# LDAQ-MOD-DAC4.net
KiCad netlist of a schematic drawn in EAGLE
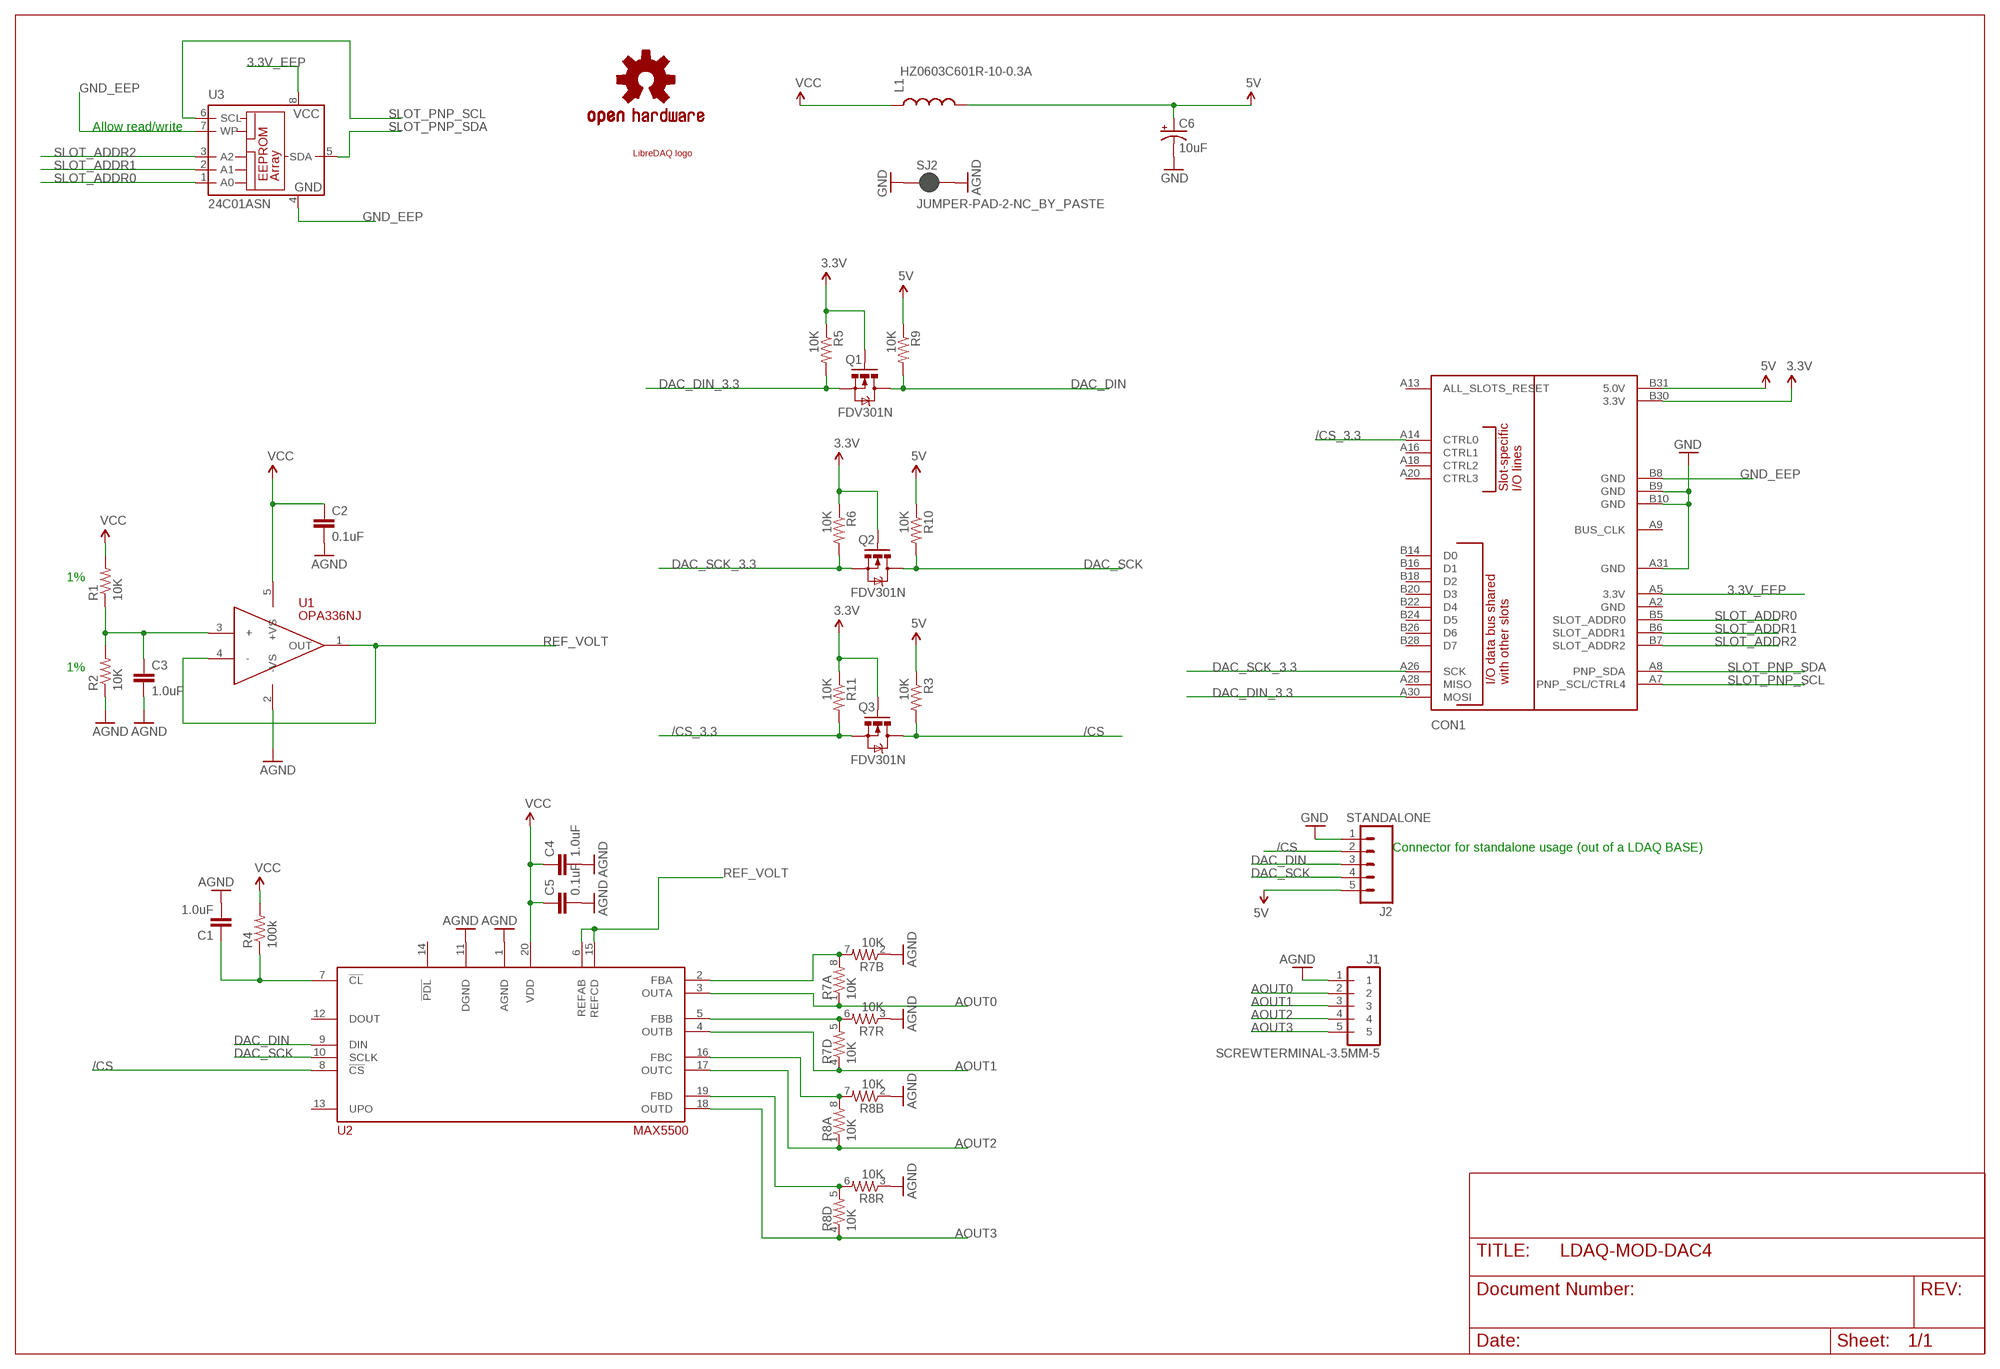
[diagram p0: schematic, sheet 1]

(export (version "E")
  (design (tool "Eeschema 10.0.6"))
  (components
    (comp (ref "C1")
      (value "1.0uF")
      (footprint "eagle-import:0603-CAP")
      (libsource (lib "eagle-import") (part "1.0UF-16V-10%(0603)"))
    )
    (comp (ref "C2")
      (value "0.1uF")
      (footprint "eagle-import:0603-CAP")
      (libsource (lib "eagle-import") (part "0.1UF-25V(+80/-20%)(0603)"))
    )
    (comp (ref "C3")
      (value "1.0uF")
      (footprint "eagle-import:0603-CAP")
      (libsource (lib "eagle-import") (part "1.0UF-16V-10%(0603)"))
    )
    (comp (ref "C4")
      (value "1.0uF")
      (footprint "eagle-import:0603-CAP")
      (libsource (lib "eagle-import") (part "1.0UF-16V-10%(0603)"))
    )
    (comp (ref "C5")
      (value "0.1uF")
      (footprint "eagle-import:0603-CAP")
      (libsource (lib "eagle-import") (part "0.1UF-25V(+80/-20%)(0603)"))
    )
    (comp (ref "C6")
      (value "10uF")
      (footprint "eagle-import:EIA3216")
      (libsource (lib "eagle-import") (part "CAP_POL1206"))
    )
    (comp (ref "CON1")
      (value "BOARD")
      (footprint "eagle-import:PCI-E_64_EDGE_63X50_PADS-ONLY")
      (libsource (lib "eagle-import") (part "LIBREDAQ_DAUGHTER_BOARDPCIE-64-SIZE2-PADS"))
    )
    (comp (ref "J1")
      (value "SCREWTERMINAL-3.5MM-5")
      (footprint "eagle-import:SCREWTERMINAL-3.5MM-5")
      (libsource (lib "eagle-import") (part "SCREWTERMINAL-3.5MM-5"))
    )
    (comp (ref "J2")
      (value "STANDALONE")
      (footprint "eagle-import:1X05_LOCK")
      (libsource (lib "eagle-import") (part "M05LOCK"))
    )
    (comp (ref "L1")
      (value "HZ0603C601R-10-0.3A")
      (footprint "eagle-import:0603")
      (libsource (lib "eagle-import") (part "INDUCTOR0603"))
    )
    (comp (ref "LOGO1")
      (value "OSHW-LOGOL")
      (footprint "eagle-import:OSHW-LOGO-L")
      (libsource (lib "eagle-import") (part "OSHW-LOGOL"))
    )
    (comp (ref "Q1")
      (value "FDV301N")
      (footprint "eagle-import:SOT23-3")
      (libsource (lib "eagle-import") (part "MOSFET-NCHANNELSMD"))
    )
    (comp (ref "Q2")
      (value "FDV301N")
      (footprint "eagle-import:SOT23-3")
      (libsource (lib "eagle-import") (part "MOSFET-NCHANNELSMD"))
    )
    (comp (ref "Q3")
      (value "FDV301N")
      (footprint "eagle-import:SOT23-3")
      (libsource (lib "eagle-import") (part "MOSFET-NCHANNELSMD"))
    )
    (comp (ref "R1")
      (value "10K")
      (footprint "eagle-import:0603-RES")
      (libsource (lib "eagle-import") (part "10KOHM-1/10W-1%(0603)0603"))
    )
    (comp (ref "R2")
      (value "10K")
      (footprint "eagle-import:0603-RES")
      (libsource (lib "eagle-import") (part "10KOHM-1/10W-1%(0603)0603"))
    )
    (comp (ref "R3")
      (value "10K")
      (footprint "eagle-import:0603-RES")
      (libsource (lib "eagle-import") (part "RESISTOR0603-RES"))
    )
    (comp (ref "R4")
      (value "100k")
      (footprint "eagle-import:0603-RES")
      (libsource (lib "eagle-import") (part "100KOHM-1/10W-1%(0603)"))
    )
    (comp (ref "R5")
      (value "10K")
      (footprint "eagle-import:0603-RES")
      (libsource (lib "eagle-import") (part "RESISTOR0603-RES"))
    )
    (comp (ref "R6")
      (value "10K")
      (footprint "eagle-import:0603-RES")
      (libsource (lib "eagle-import") (part "RESISTOR0603-RES"))
    )
    (comp (ref "R7")
      (value "10K")
      (footprint "eagle-import:0603-ARV")
      (libsource (lib "eagle-import") (part "RESISTOR-ARRAY0603-ARV"))
    )
    (comp (ref "R8")
      (value "10K")
      (footprint "eagle-import:0603-ARV")
      (libsource (lib "eagle-import") (part "RESISTOR-ARRAY0603-ARV"))
    )
    (comp (ref "R9")
      (value "10K")
      (footprint "eagle-import:0603-RES")
      (libsource (lib "eagle-import") (part "RESISTOR0603-RES"))
    )
    (comp (ref "R10")
      (value "10K")
      (footprint "eagle-import:0603-RES")
      (libsource (lib "eagle-import") (part "RESISTOR0603-RES"))
    )
    (comp (ref "R11")
      (value "10K")
      (footprint "eagle-import:0603-RES")
      (libsource (lib "eagle-import") (part "RESISTOR0603-RES"))
    )
    (comp (ref "SJ2")
      (value "JUMPER-PAD-2-NC_BY_PASTE")
      (footprint "eagle-import:PAD-JUMPER-2-NC_BY_PASTE_YES_SILK")
      (libsource (lib "eagle-import") (part "JUMPER-PAD-2-NC_BY_PASTE"))
    )
    (comp (ref "U$1")
      (value "LIBREDAQ_LOGO_MINILOGO_GENERIC")
      (footprint "eagle-import:LIBREDAQ_LOGO")
      (libsource (lib "eagle-import") (part "LIBREDAQ_LOGO_MINILOGO_GENERIC"))
    )
    (comp (ref "U1")
      (value "OPA336NJ")
      (footprint "eagle-import:SOT23-5")
      (libsource (lib "eagle-import") (part "OPA336NJ"))
    )
    (comp (ref "U2")
      (value "MAX5500")
      (footprint "eagle-import:SSOP20")
      (libsource (lib "eagle-import") (part "MAX5500"))
    )
    (comp (ref "U3")
      (value "24C01ASN")
      (footprint "eagle-import:SO-08")
      (fields (field (name "MPN") "AT24C01BN-SH-B"))
      (libsource (lib "eagle-import") (part "24CSN01A"))
    )
  )
  (nets
    (net (code "1") (name "/3.3V_EEP") (class "Default")
      (node (ref "CON1") (pin "A5") (pinfunction "3.3V_A5") (pintype "bidirectional"))
      (node (ref "U3") (pin "8") (pinfunction "VCC_8") (pintype "power_in"))
    )
    (net (code "2") (name "/AOUT0") (class "Default")
      (node (ref "J1") (pin "2") (pinfunction "2_2") (pintype "bidirectional"))
      (node (ref "R7") (pin "1") (pinfunction "1_1") (pintype "passive"))
      (node (ref "U2") (pin "3") (pinfunction "OUTA_3") (pintype "bidirectional"))
    )
    (net (code "3") (name "/AOUT1") (class "Default")
      (node (ref "J1") (pin "3") (pinfunction "3_3") (pintype "bidirectional"))
      (node (ref "R7") (pin "4") (pinfunction "1_4") (pintype "passive"))
      (node (ref "U2") (pin "4") (pinfunction "OUTB_4") (pintype "bidirectional"))
    )
    (net (code "4") (name "/AOUT2") (class "Default")
      (node (ref "J1") (pin "4") (pinfunction "4_4") (pintype "bidirectional"))
      (node (ref "R8") (pin "1") (pinfunction "1_1") (pintype "passive"))
      (node (ref "U2") (pin "17") (pinfunction "OUTC_17") (pintype "bidirectional"))
    )
    (net (code "5") (name "/AOUT3") (class "Default")
      (node (ref "J1") (pin "5") (pinfunction "5_5") (pintype "bidirectional"))
      (node (ref "R8") (pin "4") (pinfunction "1_4") (pintype "passive"))
      (node (ref "U2") (pin "18") (pinfunction "OUTD_18") (pintype "bidirectional"))
    )
    (net (code "6") (name "/DAC_DIN") (class "Default")
      (node (ref "J2") (pin "3") (pinfunction "3_3") (pintype "passive"))
      (node (ref "Q1") (pin "3") (pinfunction "D_3") (pintype "passive"))
      (node (ref "R9") (pin "2") (pinfunction "2_2") (pintype "passive"))
      (node (ref "U2") (pin "9") (pinfunction "DIN_9") (pintype "bidirectional"))
    )
    (net (code "7") (name "/DAC_DIN_3.3") (class "Default")
      (node (ref "CON1") (pin "A30") (pinfunction "MOSI_A30") (pintype "bidirectional"))
      (node (ref "Q1") (pin "2") (pinfunction "S_2") (pintype "passive"))
      (node (ref "R5") (pin "2") (pinfunction "2_2") (pintype "passive"))
    )
    (net (code "8") (name "/DAC_SCK") (class "Default")
      (node (ref "J2") (pin "4") (pinfunction "4_4") (pintype "passive"))
      (node (ref "Q2") (pin "3") (pinfunction "D_3") (pintype "passive"))
      (node (ref "R10") (pin "2") (pinfunction "2_2") (pintype "passive"))
      (node (ref "U2") (pin "10") (pinfunction "SCLK_10") (pintype "bidirectional"))
    )
    (net (code "9") (name "/DAC_SCK_3.3") (class "Default")
      (node (ref "CON1") (pin "A26") (pinfunction "SCK_A26") (pintype "bidirectional"))
      (node (ref "Q2") (pin "2") (pinfunction "S_2") (pintype "passive"))
      (node (ref "R6") (pin "2") (pinfunction "2_2") (pintype "passive"))
    )
    (net (code "10") (name "/GND_EEP") (class "Default")
      (node (ref "CON1") (pin "B8") (pinfunction "GND_B8") (pintype "bidirectional"))
      (node (ref "U3") (pin "4") (pinfunction "GND_4") (pintype "power_in"))
      (node (ref "U3") (pin "7") (pinfunction "WP_7") (pintype "input"))
    )
    (net (code "11") (name "/REF_VOLT") (class "Default")
      (node (ref "U1") (pin "1") (pinfunction "OUT_1") (pintype "bidirectional"))
      (node (ref "U1") (pin "4") (pinfunction "-_4") (pintype "bidirectional"))
      (node (ref "U2") (pin "15") (pinfunction "REFCD_15") (pintype "bidirectional"))
      (node (ref "U2") (pin "6") (pinfunction "REFAB_6") (pintype "bidirectional"))
    )
    (net (code "12") (name "/SLOT_ADDR0") (class "Default")
      (node (ref "CON1") (pin "B5") (pinfunction "SLOT_ADDR0_B5") (pintype "bidirectional"))
      (node (ref "U3") (pin "1") (pinfunction "A0_1") (pintype "input"))
    )
    (net (code "13") (name "/SLOT_ADDR1") (class "Default")
      (node (ref "CON1") (pin "B6") (pinfunction "SLOT_ADDR1_B6") (pintype "bidirectional"))
      (node (ref "U3") (pin "2") (pinfunction "A1_2") (pintype "input"))
    )
    (net (code "14") (name "/SLOT_ADDR2") (class "Default")
      (node (ref "CON1") (pin "B7") (pinfunction "SLOT_ADDR2_B7") (pintype "bidirectional"))
      (node (ref "U3") (pin "3") (pinfunction "A2_3") (pintype "input"))
    )
    (net (code "15") (name "/SLOT_PNP_SCL") (class "Default")
      (node (ref "CON1") (pin "A7") (pinfunction "PNP_SCL/CTRL4_A7") (pintype "bidirectional"))
      (node (ref "U3") (pin "6") (pinfunction "SCL_6") (pintype "input"))
    )
    (net (code "16") (name "/SLOT_PNP_SDA") (class "Default")
      (node (ref "CON1") (pin "A8") (pinfunction "PNP_SDA_A8") (pintype "bidirectional"))
      (node (ref "U3") (pin "5") (pinfunction "SDA_5") (pintype "bidirectional"))
    )
    (net (code "17") (name "/{slash}CS") (class "Default")
      (node (ref "J2") (pin "2") (pinfunction "2_2") (pintype "passive"))
      (node (ref "Q3") (pin "3") (pinfunction "D_3") (pintype "passive"))
      (node (ref "R3") (pin "2") (pinfunction "2_2") (pintype "passive"))
      (node (ref "U2") (pin "8") (pinfunction "~{CS}_8") (pintype "bidirectional"))
    )
    (net (code "18") (name "/{slash}CS_3.3") (class "Default")
      (node (ref "CON1") (pin "A14") (pinfunction "CTRL0_A14") (pintype "bidirectional"))
      (node (ref "Q3") (pin "2") (pinfunction "S_2") (pintype "passive"))
      (node (ref "R11") (pin "2") (pinfunction "2_2") (pintype "passive"))
    )
    (net (code "19") (name "3.3V") (class "Default")
      (node (ref "CON1") (pin "B30") (pinfunction "3.3V_B30") (pintype "bidirectional"))
      (node (ref "Q1") (pin "1") (pinfunction "G_1") (pintype "passive"))
      (node (ref "Q2") (pin "1") (pinfunction "G_1") (pintype "passive"))
      (node (ref "Q3") (pin "1") (pinfunction "G_1") (pintype "passive"))
      (node (ref "R11") (pin "1") (pinfunction "1_1") (pintype "passive"))
      (node (ref "R5") (pin "1") (pinfunction "1_1") (pintype "passive"))
      (node (ref "R6") (pin "1") (pinfunction "1_1") (pintype "passive"))
    )
    (net (code "20") (name "5V") (class "Default")
      (node (ref "C6") (pin "A") (pinfunction "+_A") (pintype "passive"))
      (node (ref "CON1") (pin "B31") (pinfunction "5.0V_B31") (pintype "bidirectional"))
      (node (ref "J2") (pin "5") (pinfunction "5_5") (pintype "passive"))
      (node (ref "L1") (pin "2") (pinfunction "2_2") (pintype "passive"))
      (node (ref "R10") (pin "1") (pinfunction "1_1") (pintype "passive"))
      (node (ref "R3") (pin "1") (pinfunction "1_1") (pintype "passive"))
      (node (ref "R9") (pin "1") (pinfunction "1_1") (pintype "passive"))
    )
    (net (code "21") (name "AGND") (class "Default")
      (node (ref "C1") (pin "2") (pinfunction "2_2") (pintype "passive"))
      (node (ref "C2") (pin "2") (pinfunction "2_2") (pintype "passive"))
      (node (ref "C3") (pin "2") (pinfunction "2_2") (pintype "passive"))
      (node (ref "C4") (pin "2") (pinfunction "2_2") (pintype "passive"))
      (node (ref "C5") (pin "2") (pinfunction "2_2") (pintype "passive"))
      (node (ref "J1") (pin "1") (pinfunction "1_1") (pintype "bidirectional"))
      (node (ref "R2") (pin "1") (pinfunction "1_1") (pintype "passive"))
      (node (ref "R7") (pin "2") (pinfunction "1_2") (pintype "passive"))
      (node (ref "R7") (pin "3") (pinfunction "1_3") (pintype "passive"))
      (node (ref "R8") (pin "2") (pinfunction "1_2") (pintype "passive"))
      (node (ref "R8") (pin "3") (pinfunction "1_3") (pintype "passive"))
      (node (ref "SJ2") (pin "2") (pinfunction "2_2") (pintype "passive"))
      (node (ref "U1") (pin "2") (pinfunction "-VS_2") (pintype "bidirectional"))
      (node (ref "U2") (pin "1") (pinfunction "AGND_1") (pintype "bidirectional"))
      (node (ref "U2") (pin "11") (pinfunction "DGND_11") (pintype "bidirectional"))
    )
    (net (code "22") (name "GND") (class "Default")
      (node (ref "C6") (pin "C") (pinfunction "-_C") (pintype "passive"))
      (node (ref "CON1") (pin "A31") (pinfunction "GND_A31") (pintype "bidirectional"))
      (node (ref "CON1") (pin "B10") (pinfunction "GND_B10") (pintype "bidirectional"))
      (node (ref "CON1") (pin "B9") (pinfunction "GND_B9") (pintype "bidirectional"))
      (node (ref "J2") (pin "1") (pinfunction "1_1") (pintype "passive"))
      (node (ref "SJ2") (pin "1") (pinfunction "1_1") (pintype "passive"))
    )
    (net (code "23") (name "Net-(R7A-2)") (class "Default")
      (node (ref "R7") (pin "7") (pinfunction "2_7") (pintype "passive"))
      (node (ref "R7") (pin "8") (pinfunction "2_8") (pintype "passive"))
      (node (ref "U2") (pin "2") (pinfunction "FBA_2") (pintype "bidirectional"))
    )
    (net (code "24") (name "Net-(R7C-2)") (class "Default")
      (node (ref "R7") (pin "5") (pinfunction "2_5") (pintype "passive"))
      (node (ref "R7") (pin "6") (pinfunction "2_6") (pintype "passive"))
      (node (ref "U2") (pin "5") (pinfunction "FBB_5") (pintype "bidirectional"))
    )
    (net (code "25") (name "Net-(R8A-2)") (class "Default")
      (node (ref "R8") (pin "7") (pinfunction "2_7") (pintype "passive"))
      (node (ref "R8") (pin "8") (pinfunction "2_8") (pintype "passive"))
      (node (ref "U2") (pin "16") (pinfunction "FBC_16") (pintype "bidirectional"))
    )
    (net (code "26") (name "Net-(R8C-2)") (class "Default")
      (node (ref "R8") (pin "5") (pinfunction "2_5") (pintype "passive"))
      (node (ref "R8") (pin "6") (pinfunction "2_6") (pintype "passive"))
      (node (ref "U2") (pin "19") (pinfunction "FBD_19") (pintype "bidirectional"))
    )
    (net (code "27") (name "Net-(U1-+)") (class "Default")
      (node (ref "C3") (pin "1") (pinfunction "1_1") (pintype "passive"))
      (node (ref "R1") (pin "1") (pinfunction "1_1") (pintype "passive"))
      (node (ref "R2") (pin "2") (pinfunction "2_2") (pintype "passive"))
      (node (ref "U1") (pin "3") (pinfunction "+_3") (pintype "bidirectional"))
    )
    (net (code "28") (name "Net-(U2-~{CL})") (class "Default")
      (node (ref "C1") (pin "1") (pinfunction "1_1") (pintype "passive"))
      (node (ref "R4") (pin "1") (pinfunction "1_1") (pintype "passive"))
      (node (ref "U2") (pin "7") (pinfunction "~{CL}_7") (pintype "bidirectional"))
    )
    (net (code "29") (name "VCC") (class "Default")
      (node (ref "C2") (pin "1") (pinfunction "1_1") (pintype "passive"))
      (node (ref "C4") (pin "1") (pinfunction "1_1") (pintype "passive"))
      (node (ref "C5") (pin "1") (pinfunction "1_1") (pintype "passive"))
      (node (ref "L1") (pin "1") (pinfunction "1_1") (pintype "passive"))
      (node (ref "R1") (pin "2") (pinfunction "2_2") (pintype "passive"))
      (node (ref "R4") (pin "2") (pinfunction "2_2") (pintype "passive"))
      (node (ref "U1") (pin "5") (pinfunction "+VS_5") (pintype "bidirectional"))
      (node (ref "U2") (pin "20") (pinfunction "VDD_20") (pintype "bidirectional"))
    )
    (net (code "30") (name "unconnected-(CON1-ALL_SLOTS_RESET-PadA13)") (class "Default")
      (node (ref "CON1") (pin "A13") (pinfunction "ALL_SLOTS_RESET_A13") (pintype "bidirectional"))
    )
    (net (code "31") (name "unconnected-(CON1-BUS_CLK-PadA9)") (class "Default")
      (node (ref "CON1") (pin "A9") (pinfunction "BUS_CLK_A9") (pintype "bidirectional"))
    )
    (net (code "32") (name "unconnected-(CON1-CTRL1-PadA16)") (class "Default")
      (node (ref "CON1") (pin "A16") (pinfunction "CTRL1_A16") (pintype "bidirectional"))
    )
    (net (code "33") (name "unconnected-(CON1-CTRL2-PadA18)") (class "Default")
      (node (ref "CON1") (pin "A18") (pinfunction "CTRL2_A18") (pintype "bidirectional"))
    )
    (net (code "34") (name "unconnected-(CON1-CTRL3-PadA20)") (class "Default")
      (node (ref "CON1") (pin "A20") (pinfunction "CTRL3_A20") (pintype "bidirectional"))
    )
    (net (code "35") (name "unconnected-(CON1-D0-PadB14)") (class "Default")
      (node (ref "CON1") (pin "B14") (pinfunction "D0_B14") (pintype "bidirectional"))
    )
    (net (code "36") (name "unconnected-(CON1-D1-PadB16)") (class "Default")
      (node (ref "CON1") (pin "B16") (pinfunction "D1_B16") (pintype "bidirectional"))
    )
    (net (code "37") (name "unconnected-(CON1-D2-PadB18)") (class "Default")
      (node (ref "CON1") (pin "B18") (pinfunction "D2_B18") (pintype "bidirectional"))
    )
    (net (code "38") (name "unconnected-(CON1-D3-PadB20)") (class "Default")
      (node (ref "CON1") (pin "B20") (pinfunction "D3_B20") (pintype "bidirectional"))
    )
    (net (code "39") (name "unconnected-(CON1-D4-PadB22)") (class "Default")
      (node (ref "CON1") (pin "B22") (pinfunction "D4_B22") (pintype "bidirectional"))
    )
    (net (code "40") (name "unconnected-(CON1-D5-PadB24)") (class "Default")
      (node (ref "CON1") (pin "B24") (pinfunction "D5_B24") (pintype "bidirectional"))
    )
    (net (code "41") (name "unconnected-(CON1-D6-PadB26)") (class "Default")
      (node (ref "CON1") (pin "B26") (pinfunction "D6_B26") (pintype "bidirectional"))
    )
    (net (code "42") (name "unconnected-(CON1-D7-PadB28)") (class "Default")
      (node (ref "CON1") (pin "B28") (pinfunction "D7_B28") (pintype "bidirectional"))
    )
    (net (code "43") (name "unconnected-(CON1-GND-PadA2)") (class "Default")
      (node (ref "CON1") (pin "A2") (pinfunction "GND_A2") (pintype "bidirectional"))
    )
    (net (code "44") (name "unconnected-(CON1-MISO-PadA28)") (class "Default")
      (node (ref "CON1") (pin "A28") (pinfunction "MISO_A28") (pintype "bidirectional"))
    )
    (net (code "45") (name "unconnected-(U2-DOUT-Pad12)") (class "Default")
      (node (ref "U2") (pin "12") (pinfunction "DOUT_12") (pintype "bidirectional"))
    )
    (net (code "46") (name "unconnected-(U2-UPO-Pad13)") (class "Default")
      (node (ref "U2") (pin "13") (pinfunction "UPO_13") (pintype "bidirectional"))
    )
    (net (code "47") (name "unconnected-(U2-~{PDL}-Pad14)") (class "Default")
      (node (ref "U2") (pin "14") (pinfunction "~{PDL}_14") (pintype "bidirectional"))
    )
  )
)
